# RTU_LMG_IO_Expanders.net
KiCad netlist of a schematic drawn in Altium Designer
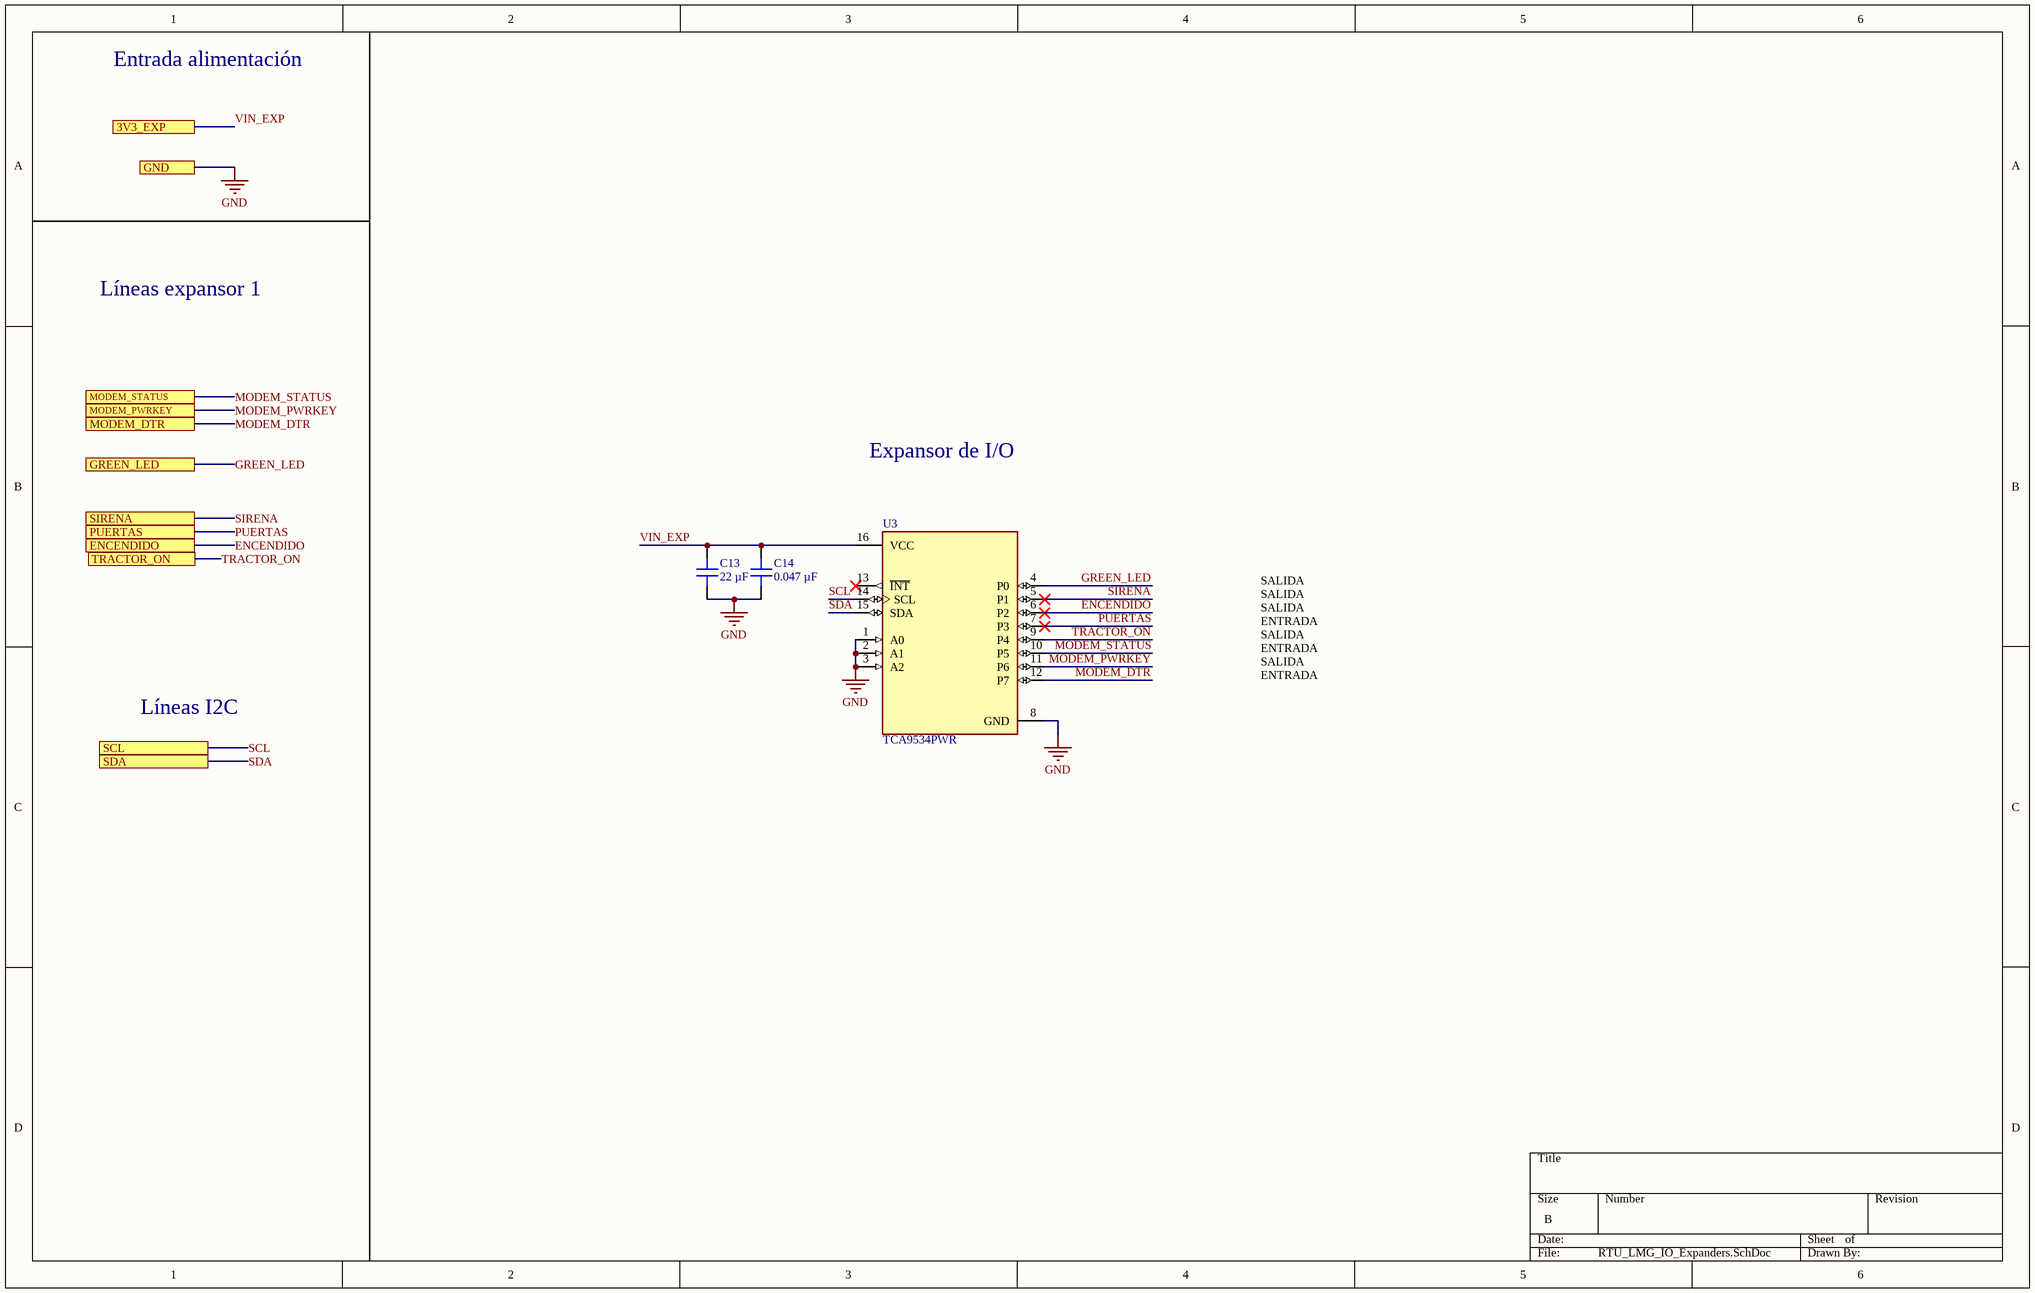
[diagram p0: RTU_LMG_IO_Expanders.SchDoc]

(export (version "E")
  (design (tool "Eeschema 10.0.6"))
  (components
    (comp (ref "C13")
      (value "22 µF")
      (footprint "CAP 0805_2012")
      (description "CAP CER 22UF 16V X5R 0805")
      (fields
        (field (name "PART NUMBER") "CL21A226MOCLRNC")
        (field (name "MANUFACTURER") "Samsung Electro-Mechanics")
      )
      (libsource (lib "Celestial Altium Library - altium_library") (part "Capacitor"))
    )
    (comp (ref "C14")
      (value "0.047 µF")
      (footprint "CAP 0603_1608")
      (description "CAP CER 0.047UF 100V X7R 0603")
      (fields (field (name "PART NUMBER") "885012206118") (field (name "MANUFACTURER") "Würth Elektronik"))
      (libsource (lib "Celestial Altium Library - altium_library") (part "Capacitor"))
    )
    (comp (ref "U3")
      (value "TCA9534PWR")
      (footprint "16-TSSOP")
      (libsource (lib "DIN_DC_Base_Board_components") (part "TCA9534PWR"))
    )
  )
  (nets
    (net (code "1") (name "/ENCENDIDO") (class "Default")
      (node (ref "U3") (pin "6") (pinfunction "P2_6") (pintype "bidirectional"))
    )
    (net (code "2") (name "/GREEN_LED") (class "Default")
      (node (ref "U3") (pin "4") (pinfunction "P0_4") (pintype "bidirectional"))
    )
    (net (code "3") (name "/MODEM_DTR") (class "Default")
      (node (ref "U3") (pin "12") (pinfunction "P7_12") (pintype "bidirectional"))
    )
    (net (code "4") (name "/MODEM_PWRKEY") (class "Default")
      (node (ref "U3") (pin "11") (pinfunction "P6_11") (pintype "bidirectional"))
    )
    (net (code "5") (name "/MODEM_STATUS") (class "Default")
      (node (ref "U3") (pin "10") (pinfunction "P5_10") (pintype "bidirectional"))
    )
    (net (code "6") (name "/PUERTAS") (class "Default")
      (node (ref "U3") (pin "7") (pinfunction "P3_7") (pintype "bidirectional"))
    )
    (net (code "7") (name "/SCL") (class "Default")
      (node (ref "U3") (pin "14") (pinfunction "SCL_14") (pintype "bidirectional"))
    )
    (net (code "8") (name "/SDA") (class "Default")
      (node (ref "U3") (pin "15") (pinfunction "SDA_15") (pintype "bidirectional"))
    )
    (net (code "9") (name "/SIRENA") (class "Default")
      (node (ref "U3") (pin "5") (pinfunction "P1_5") (pintype "bidirectional"))
    )
    (net (code "10") (name "/TRACTOR_ON") (class "Default")
      (node (ref "U3") (pin "9") (pinfunction "P4_9") (pintype "bidirectional"))
    )
    (net (code "11") (name "/VIN_EXP") (class "Default")
      (node (ref "C13") (pin "2") (pinfunction "2_2") (pintype "passive"))
      (node (ref "C14") (pin "2") (pinfunction "2_2") (pintype "passive"))
      (node (ref "U3") (pin "16") (pinfunction "VCC_16") (pintype "power_in"))
    )
    (net (code "12") (name "GND") (class "Default")
      (node (ref "C13") (pin "1") (pinfunction "1_1") (pintype "passive"))
      (node (ref "C14") (pin "1") (pinfunction "1_1") (pintype "passive"))
      (node (ref "U3") (pin "1") (pinfunction "A0_1") (pintype "input"))
      (node (ref "U3") (pin "2") (pinfunction "A1_2") (pintype "input"))
      (node (ref "U3") (pin "3") (pinfunction "A2_3") (pintype "input"))
      (node (ref "U3") (pin "8") (pinfunction "GND_8") (pintype "power_in"))
    )
    (net (code "13") (name "unconnected-(U3-~{INT}-Pad13)") (class "Default")
      (node (ref "U3") (pin "13") (pinfunction "~{INT}_13") (pintype "output+no_connect"))
    )
  )
)
